# rizon.net
KiCad netlist of a schematic drawn in EAGLE
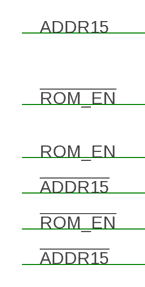
[diagram p0: schematic, sheet 1, part 1 of 2]
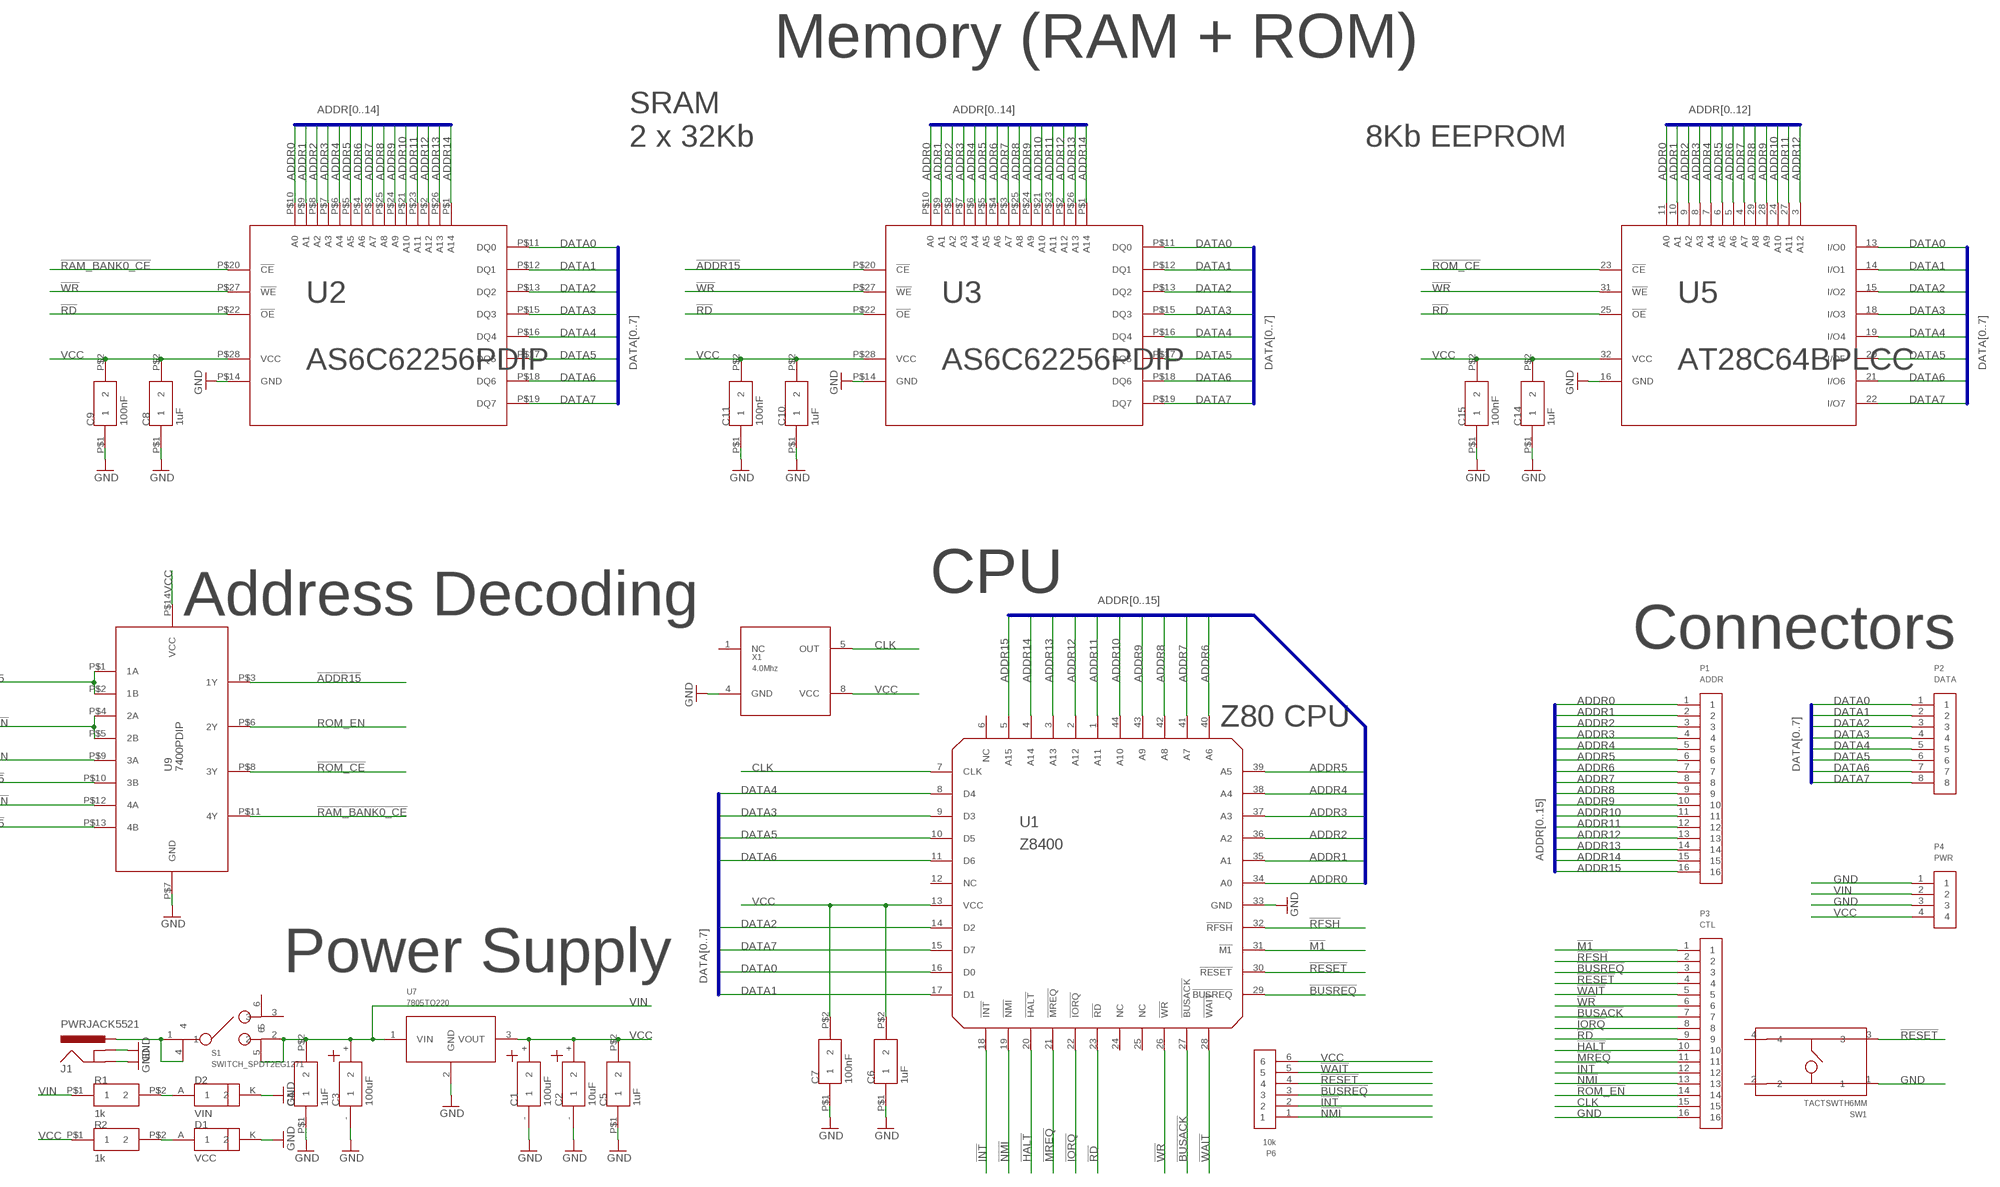
[diagram p1: schematic, sheet 1, part 2 of 2]

(export (version "E")
  (design (tool "Eeschema 10.0.6"))
  (components
    (comp (ref "C1")
      (value "100uF")
      (footprint "eagle-import:RADCAP_5MM")
      (libsource (lib "eagle-import") (part "CAP_POLARIZEDRAD_5MM"))
    )
    (comp (ref "C2")
      (value "10uF")
      (footprint "eagle-import:RADCAP_5MM")
      (libsource (lib "eagle-import") (part "CAP_POLARIZEDRAD_5MM"))
    )
    (comp (ref "C3")
      (value "100uF")
      (footprint "eagle-import:RADCAP_5MM")
      (libsource (lib "eagle-import") (part "CAP_POLARIZEDRAD_5MM"))
    )
    (comp (ref "C4")
      (value "1uF")
      (footprint "eagle-import:CAP_508")
      (libsource (lib "eagle-import") (part "CAP508"))
    )
    (comp (ref "C5")
      (value "1uF")
      (footprint "eagle-import:CAP_508")
      (libsource (lib "eagle-import") (part "CAP508"))
    )
    (comp (ref "C6")
      (value "1uF")
      (footprint "eagle-import:CAP_508")
      (libsource (lib "eagle-import") (part "CAP508"))
    )
    (comp (ref "C7")
      (value "100nF")
      (footprint "eagle-import:CAP_DISC")
      (libsource (lib "eagle-import") (part "CAPDISC"))
    )
    (comp (ref "C8")
      (value "1uF")
      (footprint "eagle-import:CAP_508")
      (libsource (lib "eagle-import") (part "CAP508"))
    )
    (comp (ref "C9")
      (value "100nF")
      (footprint "eagle-import:CAP_DISC")
      (libsource (lib "eagle-import") (part "CAPDISC"))
    )
    (comp (ref "C10")
      (value "1uF")
      (footprint "eagle-import:CAP_508")
      (libsource (lib "eagle-import") (part "CAP508"))
    )
    (comp (ref "C11")
      (value "100nF")
      (footprint "eagle-import:CAP_DISC")
      (libsource (lib "eagle-import") (part "CAPDISC"))
    )
    (comp (ref "C14")
      (value "1uF")
      (footprint "eagle-import:CAP_508")
      (libsource (lib "eagle-import") (part "CAP508"))
    )
    (comp (ref "C15")
      (value "100nF")
      (footprint "eagle-import:CAP_DISC")
      (libsource (lib "eagle-import") (part "CAPDISC"))
    )
    (comp (ref "D1")
      (value "VCC")
      (footprint "eagle-import:LED5MM")
      (libsource (lib "eagle-import") (part "LED5MM"))
    )
    (comp (ref "D2")
      (value "VIN")
      (footprint "eagle-import:LED5MM")
      (libsource (lib "eagle-import") (part "LED5MM"))
    )
    (comp (ref "J1")
      (value "PWRJACK5521")
      (footprint "eagle-import:PWRJACK_5521")
      (libsource (lib "eagle-import") (part "PWRJACK5521"))
    )
    (comp (ref "P1")
      (value "ADDR")
      (footprint "eagle-import:PIN_16")
      (libsource (lib "eagle-import") (part "PIN_16"))
    )
    (comp (ref "P2")
      (value "DATA")
      (footprint "eagle-import:PIN_8")
      (libsource (lib "eagle-import") (part "PIN_8"))
    )
    (comp (ref "P3")
      (value "CTL")
      (footprint "eagle-import:PIN_16")
      (libsource (lib "eagle-import") (part "PIN_16"))
    )
    (comp (ref "P4")
      (value "PWR")
      (footprint "eagle-import:PIN_4")
      (libsource (lib "eagle-import") (part "PIN_4"))
    )
    (comp (ref "P6")
      (value "10k")
      (footprint "eagle-import:PIN_6")
      (libsource (lib "eagle-import") (part "PIN_61LINE"))
    )
    (comp (ref "R1")
      (value "1k")
      (footprint "eagle-import:RES8MM")
      (libsource (lib "eagle-import") (part "RES8MM"))
    )
    (comp (ref "R2")
      (value "1k")
      (footprint "eagle-import:RES8MM")
      (libsource (lib "eagle-import") (part "RES8MM"))
    )
    (comp (ref "S1")
      (value "SWITCH_SPDT2EG1271")
      (footprint "eagle-import:EG1271")
      (libsource (lib "eagle-import") (part "SWITCH_SPDT2EG1271"))
    )
    (comp (ref "SW1")
      (value "TACTSWTH6MM")
      (footprint "eagle-import:SWITCH_6MM")
      (libsource (lib "eagle-import") (part "TACTSWTH6MM"))
    )
    (comp (ref "U1")
      (value "Z8400")
      (footprint "eagle-import:PLCC-S44-SOCKET")
      (libsource (lib "eagle-import") (part "Z8400"))
    )
    (comp (ref "U2")
      (value "AS6C62256PDIP")
      (footprint "eagle-import:PDIP28-600")
      (libsource (lib "eagle-import") (part "AS6C62256PDIP"))
    )
    (comp (ref "U3")
      (value "AS6C62256PDIP")
      (footprint "eagle-import:PDIP28-600")
      (libsource (lib "eagle-import") (part "AS6C62256PDIP"))
    )
    (comp (ref "U5")
      (value "AT28C64BPLCC")
      (footprint "eagle-import:PLCC-S32--SOCKET")
      (libsource (lib "eagle-import") (part "AT28C64BPLCC"))
    )
    (comp (ref "U7")
      (value "7805TO220")
      (footprint "eagle-import:TO220V")
      (libsource (lib "eagle-import") (part "7805TO220"))
    )
    (comp (ref "U9")
      (value "7400PDIP")
      (footprint "eagle-import:PDIP14")
      (libsource (lib "eagle-import") (part "7400PDIP"))
    )
    (comp (ref "X1")
      (value "4.0Mhz")
      (footprint "eagle-import:OSC127")
      (libsource (lib "eagle-import") (part "OSC412.7"))
    )
  )
  (nets
    (net (code "1") (name "/ADDR0") (class "Default")
      (node (ref "P1") (pin "1") (pinfunction "1_1") (pintype "bidirectional"))
      (node (ref "U1") (pin "34") (pinfunction "A0_34") (pintype "bidirectional"))
      (node (ref "U2") (pin "P$10") (pinfunction "A0_P$10") (pintype "bidirectional"))
      (node (ref "U3") (pin "P$10") (pinfunction "A0_P$10") (pintype "bidirectional"))
      (node (ref "U5") (pin "11") (pinfunction "A0_11") (pintype "bidirectional"))
    )
    (net (code "2") (name "/ADDR1") (class "Default")
      (node (ref "P1") (pin "2") (pinfunction "2_2") (pintype "bidirectional"))
      (node (ref "U1") (pin "35") (pinfunction "A1_35") (pintype "bidirectional"))
      (node (ref "U2") (pin "P$9") (pinfunction "A1_P$9") (pintype "bidirectional"))
      (node (ref "U3") (pin "P$9") (pinfunction "A1_P$9") (pintype "bidirectional"))
      (node (ref "U5") (pin "10") (pinfunction "A1_10") (pintype "bidirectional"))
    )
    (net (code "3") (name "/ADDR2") (class "Default")
      (node (ref "P1") (pin "3") (pinfunction "3_3") (pintype "bidirectional"))
      (node (ref "U1") (pin "36") (pinfunction "A2_36") (pintype "bidirectional"))
      (node (ref "U2") (pin "P$8") (pinfunction "A2_P$8") (pintype "bidirectional"))
      (node (ref "U3") (pin "P$8") (pinfunction "A2_P$8") (pintype "bidirectional"))
      (node (ref "U5") (pin "9") (pinfunction "A2_9") (pintype "bidirectional"))
    )
    (net (code "4") (name "/ADDR3") (class "Default")
      (node (ref "P1") (pin "4") (pinfunction "4_4") (pintype "bidirectional"))
      (node (ref "U1") (pin "37") (pinfunction "A3_37") (pintype "bidirectional"))
      (node (ref "U2") (pin "P$7") (pinfunction "A3_P$7") (pintype "bidirectional"))
      (node (ref "U3") (pin "P$7") (pinfunction "A3_P$7") (pintype "bidirectional"))
      (node (ref "U5") (pin "8") (pinfunction "A3_8") (pintype "bidirectional"))
    )
    (net (code "5") (name "/ADDR4") (class "Default")
      (node (ref "P1") (pin "5") (pinfunction "5_5") (pintype "bidirectional"))
      (node (ref "U1") (pin "38") (pinfunction "A4_38") (pintype "bidirectional"))
      (node (ref "U2") (pin "P$6") (pinfunction "A4_P$6") (pintype "bidirectional"))
      (node (ref "U3") (pin "P$6") (pinfunction "A4_P$6") (pintype "bidirectional"))
      (node (ref "U5") (pin "7") (pinfunction "A4_7") (pintype "bidirectional"))
    )
    (net (code "6") (name "/ADDR5") (class "Default")
      (node (ref "P1") (pin "6") (pinfunction "6_6") (pintype "bidirectional"))
      (node (ref "U1") (pin "39") (pinfunction "A5_39") (pintype "bidirectional"))
      (node (ref "U2") (pin "P$5") (pinfunction "A5_P$5") (pintype "bidirectional"))
      (node (ref "U3") (pin "P$5") (pinfunction "A5_P$5") (pintype "bidirectional"))
      (node (ref "U5") (pin "6") (pinfunction "A5_6") (pintype "bidirectional"))
    )
    (net (code "7") (name "/ADDR6") (class "Default")
      (node (ref "P1") (pin "7") (pinfunction "7_7") (pintype "bidirectional"))
      (node (ref "U1") (pin "40") (pinfunction "A6_40") (pintype "bidirectional"))
      (node (ref "U2") (pin "P$4") (pinfunction "A6_P$4") (pintype "bidirectional"))
      (node (ref "U3") (pin "P$4") (pinfunction "A6_P$4") (pintype "bidirectional"))
      (node (ref "U5") (pin "5") (pinfunction "A6_5") (pintype "bidirectional"))
    )
    (net (code "8") (name "/ADDR7") (class "Default")
      (node (ref "P1") (pin "8") (pinfunction "8_8") (pintype "bidirectional"))
      (node (ref "U1") (pin "41") (pinfunction "A7_41") (pintype "bidirectional"))
      (node (ref "U2") (pin "P$3") (pinfunction "A7_P$3") (pintype "bidirectional"))
      (node (ref "U3") (pin "P$3") (pinfunction "A7_P$3") (pintype "bidirectional"))
      (node (ref "U5") (pin "4") (pinfunction "A7_4") (pintype "bidirectional"))
    )
    (net (code "9") (name "/ADDR8") (class "Default")
      (node (ref "P1") (pin "9") (pinfunction "9_9") (pintype "bidirectional"))
      (node (ref "U1") (pin "42") (pinfunction "A8_42") (pintype "bidirectional"))
      (node (ref "U2") (pin "P$25") (pinfunction "A8_P$25") (pintype "bidirectional"))
      (node (ref "U3") (pin "P$25") (pinfunction "A8_P$25") (pintype "bidirectional"))
      (node (ref "U5") (pin "29") (pinfunction "A8_29") (pintype "bidirectional"))
    )
    (net (code "10") (name "/ADDR9") (class "Default")
      (node (ref "P1") (pin "10") (pinfunction "10_10") (pintype "bidirectional"))
      (node (ref "U1") (pin "43") (pinfunction "A9_43") (pintype "bidirectional"))
      (node (ref "U2") (pin "P$24") (pinfunction "A9_P$24") (pintype "bidirectional"))
      (node (ref "U3") (pin "P$24") (pinfunction "A9_P$24") (pintype "bidirectional"))
      (node (ref "U5") (pin "28") (pinfunction "A9_28") (pintype "bidirectional"))
    )
    (net (code "11") (name "/ADDR10") (class "Default")
      (node (ref "P1") (pin "11") (pinfunction "11_11") (pintype "bidirectional"))
      (node (ref "U1") (pin "44") (pinfunction "A10_44") (pintype "bidirectional"))
      (node (ref "U2") (pin "P$21") (pinfunction "A10_P$21") (pintype "bidirectional"))
      (node (ref "U3") (pin "P$21") (pinfunction "A10_P$21") (pintype "bidirectional"))
      (node (ref "U5") (pin "24") (pinfunction "A10_24") (pintype "bidirectional"))
    )
    (net (code "12") (name "/ADDR11") (class "Default")
      (node (ref "P1") (pin "12") (pinfunction "12_12") (pintype "bidirectional"))
      (node (ref "U1") (pin "1") (pinfunction "A11_1") (pintype "bidirectional"))
      (node (ref "U2") (pin "P$23") (pinfunction "A11_P$23") (pintype "bidirectional"))
      (node (ref "U3") (pin "P$23") (pinfunction "A11_P$23") (pintype "bidirectional"))
      (node (ref "U5") (pin "27") (pinfunction "A11_27") (pintype "bidirectional"))
    )
    (net (code "13") (name "/ADDR12") (class "Default")
      (node (ref "P1") (pin "13") (pinfunction "13_13") (pintype "bidirectional"))
      (node (ref "U1") (pin "2") (pinfunction "A12_2") (pintype "bidirectional"))
      (node (ref "U2") (pin "P$2") (pinfunction "A12_P$2") (pintype "bidirectional"))
      (node (ref "U3") (pin "P$2") (pinfunction "A12_P$2") (pintype "bidirectional"))
      (node (ref "U5") (pin "3") (pinfunction "A12_3") (pintype "bidirectional"))
    )
    (net (code "14") (name "/ADDR13") (class "Default")
      (node (ref "P1") (pin "14") (pinfunction "14_14") (pintype "bidirectional"))
      (node (ref "U1") (pin "3") (pinfunction "A13_3") (pintype "bidirectional"))
      (node (ref "U2") (pin "P$26") (pinfunction "A13_P$26") (pintype "bidirectional"))
      (node (ref "U3") (pin "P$26") (pinfunction "A13_P$26") (pintype "bidirectional"))
    )
    (net (code "15") (name "/ADDR14") (class "Default")
      (node (ref "P1") (pin "15") (pinfunction "15_15") (pintype "bidirectional"))
      (node (ref "U1") (pin "4") (pinfunction "A14_4") (pintype "bidirectional"))
      (node (ref "U2") (pin "P$1") (pinfunction "A14_P$1") (pintype "bidirectional"))
      (node (ref "U3") (pin "P$1") (pinfunction "A14_P$1") (pintype "bidirectional"))
    )
    (net (code "16") (name "/ADDR15") (class "Default")
      (node (ref "P1") (pin "16") (pinfunction "16_16") (pintype "bidirectional"))
      (node (ref "U1") (pin "5") (pinfunction "A15_5") (pintype "bidirectional"))
      (node (ref "U9") (pin "P$1") (pinfunction "1A_P$1") (pintype "bidirectional"))
      (node (ref "U9") (pin "P$2") (pinfunction "1B_P$2") (pintype "bidirectional"))
    )
    (net (code "20") (name "/CLK") (class "Default")
      (node (ref "P3") (pin "15") (pinfunction "15_15") (pintype "bidirectional"))
      (node (ref "U1") (pin "7") (pinfunction "CLK_7") (pintype "bidirectional"))
      (node (ref "X1") (pin "5") (pinfunction "OUT_5") (pintype "bidirectional"))
    )
    (net (code "21") (name "/DATA0") (class "Default")
      (node (ref "P2") (pin "1") (pinfunction "1_1") (pintype "bidirectional"))
      (node (ref "U1") (pin "16") (pinfunction "D0_16") (pintype "bidirectional"))
      (node (ref "U2") (pin "P$11") (pinfunction "DQ0_P$11") (pintype "bidirectional"))
      (node (ref "U3") (pin "P$11") (pinfunction "DQ0_P$11") (pintype "bidirectional"))
      (node (ref "U5") (pin "13") (pinfunction "I/O0_13") (pintype "bidirectional"))
    )
    (net (code "22") (name "/DATA1") (class "Default")
      (node (ref "P2") (pin "2") (pinfunction "2_2") (pintype "bidirectional"))
      (node (ref "U1") (pin "17") (pinfunction "D1_17") (pintype "bidirectional"))
      (node (ref "U2") (pin "P$12") (pinfunction "DQ1_P$12") (pintype "bidirectional"))
      (node (ref "U3") (pin "P$12") (pinfunction "DQ1_P$12") (pintype "bidirectional"))
      (node (ref "U5") (pin "14") (pinfunction "I/O1_14") (pintype "bidirectional"))
    )
    (net (code "23") (name "/DATA2") (class "Default")
      (node (ref "P2") (pin "3") (pinfunction "3_3") (pintype "bidirectional"))
      (node (ref "U1") (pin "14") (pinfunction "D2_14") (pintype "bidirectional"))
      (node (ref "U2") (pin "P$13") (pinfunction "DQ2_P$13") (pintype "bidirectional"))
      (node (ref "U3") (pin "P$13") (pinfunction "DQ2_P$13") (pintype "bidirectional"))
      (node (ref "U5") (pin "15") (pinfunction "I/O2_15") (pintype "bidirectional"))
    )
    (net (code "24") (name "/DATA3") (class "Default")
      (node (ref "P2") (pin "4") (pinfunction "4_4") (pintype "bidirectional"))
      (node (ref "U1") (pin "9") (pinfunction "D3_9") (pintype "bidirectional"))
      (node (ref "U2") (pin "P$15") (pinfunction "DQ3_P$15") (pintype "bidirectional"))
      (node (ref "U3") (pin "P$15") (pinfunction "DQ3_P$15") (pintype "bidirectional"))
      (node (ref "U5") (pin "18") (pinfunction "I/O3_18") (pintype "bidirectional"))
    )
    (net (code "25") (name "/DATA4") (class "Default")
      (node (ref "P2") (pin "5") (pinfunction "5_5") (pintype "bidirectional"))
      (node (ref "U1") (pin "8") (pinfunction "D4_8") (pintype "bidirectional"))
      (node (ref "U2") (pin "P$16") (pinfunction "DQ4_P$16") (pintype "bidirectional"))
      (node (ref "U3") (pin "P$16") (pinfunction "DQ4_P$16") (pintype "bidirectional"))
      (node (ref "U5") (pin "19") (pinfunction "I/O4_19") (pintype "bidirectional"))
    )
    (net (code "26") (name "/DATA5") (class "Default")
      (node (ref "P2") (pin "6") (pinfunction "6_6") (pintype "bidirectional"))
      (node (ref "U1") (pin "10") (pinfunction "D5_10") (pintype "bidirectional"))
      (node (ref "U2") (pin "P$17") (pinfunction "DQ5_P$17") (pintype "bidirectional"))
      (node (ref "U3") (pin "P$17") (pinfunction "DQ5_P$17") (pintype "bidirectional"))
      (node (ref "U5") (pin "20") (pinfunction "I/O5_20") (pintype "bidirectional"))
    )
    (net (code "27") (name "/DATA6") (class "Default")
      (node (ref "P2") (pin "7") (pinfunction "7_7") (pintype "bidirectional"))
      (node (ref "U1") (pin "11") (pinfunction "D6_11") (pintype "bidirectional"))
      (node (ref "U2") (pin "P$18") (pinfunction "DQ6_P$18") (pintype "bidirectional"))
      (node (ref "U3") (pin "P$18") (pinfunction "DQ6_P$18") (pintype "bidirectional"))
      (node (ref "U5") (pin "21") (pinfunction "I/O6_21") (pintype "bidirectional"))
    )
    (net (code "28") (name "/DATA7") (class "Default")
      (node (ref "P2") (pin "8") (pinfunction "8_8") (pintype "bidirectional"))
      (node (ref "U1") (pin "15") (pinfunction "D7_15") (pintype "bidirectional"))
      (node (ref "U2") (pin "P$19") (pinfunction "DQ7_P$19") (pintype "bidirectional"))
      (node (ref "U3") (pin "P$19") (pinfunction "DQ7_P$19") (pintype "bidirectional"))
      (node (ref "U5") (pin "22") (pinfunction "I/O7_22") (pintype "bidirectional"))
    )
    (net (code "30") (name "/ROM_EN") (class "Default")
      (node (ref "U9") (pin "P$6") (pinfunction "2Y_P$6") (pintype "bidirectional"))
      (node (ref "U9") (pin "P$9") (pinfunction "3A_P$9") (pintype "bidirectional"))
    )
    (net (code "31") (name "/VCC") (class "Default")
      (node (ref "C1") (pin "+") (pinfunction "2_+") (pintype "bidirectional"))
      (node (ref "C10") (pin "P$2") (pinfunction "2_P$2") (pintype "bidirectional"))
      (node (ref "C11") (pin "P$2") (pinfunction "2_P$2") (pintype "bidirectional"))
      (node (ref "C14") (pin "P$2") (pinfunction "2_P$2") (pintype "bidirectional"))
      (node (ref "C15") (pin "P$2") (pinfunction "2_P$2") (pintype "bidirectional"))
      (node (ref "C2") (pin "+") (pinfunction "2_+") (pintype "bidirectional"))
      (node (ref "C5") (pin "P$2") (pinfunction "2_P$2") (pintype "bidirectional"))
      (node (ref "C6") (pin "P$2") (pinfunction "2_P$2") (pintype "bidirectional"))
      (node (ref "C7") (pin "P$2") (pinfunction "2_P$2") (pintype "bidirectional"))
      (node (ref "C8") (pin "P$2") (pinfunction "2_P$2") (pintype "bidirectional"))
      (node (ref "C9") (pin "P$2") (pinfunction "2_P$2") (pintype "bidirectional"))
      (node (ref "P4") (pin "4") (pinfunction "4_4") (pintype "bidirectional"))
      (node (ref "P6") (pin "6") (pinfunction "6_6") (pintype "bidirectional"))
      (node (ref "R2") (pin "P$1") (pinfunction "1_P$1") (pintype "bidirectional"))
      (node (ref "U1") (pin "13") (pinfunction "VCC_13") (pintype "bidirectional"))
      (node (ref "U2") (pin "P$28") (pinfunction "VCC_P$28") (pintype "bidirectional"))
      (node (ref "U3") (pin "P$28") (pinfunction "VCC_P$28") (pintype "bidirectional"))
      (node (ref "U5") (pin "32") (pinfunction "VCC_32") (pintype "bidirectional"))
      (node (ref "U7") (pin "3") (pinfunction "VOUT_3") (pintype "bidirectional"))
      (node (ref "U9") (pin "P$14") (pinfunction "VCC_P$14") (pintype "bidirectional"))
      (node (ref "X1") (pin "8") (pinfunction "VCC_8") (pintype "bidirectional"))
    )
    (net (code "32") (name "/VIN") (class "Default")
      (node (ref "C3") (pin "+") (pinfunction "2_+") (pintype "bidirectional"))
      (node (ref "C4") (pin "P$2") (pinfunction "2_P$2") (pintype "bidirectional"))
      (node (ref "P4") (pin "2") (pinfunction "2_2") (pintype "bidirectional"))
      (node (ref "R1") (pin "P$1") (pinfunction "1_P$1") (pintype "bidirectional"))
      (node (ref "S1") (pin "2") (pinfunction "2_2") (pintype "bidirectional"))
      (node (ref "S1") (pin "5") (pinfunction "5_5") (pintype "bidirectional"))
      (node (ref "U7") (pin "1") (pinfunction "VIN_1") (pintype "bidirectional"))
    )
    (net (code "33") (name "/~{ADDR15}") (class "Default")
      (node (ref "U3") (pin "P$20") (pinfunction "~{CE}_P$20") (pintype "bidirectional"))
      (node (ref "U9") (pin "P$10") (pinfunction "3B_P$10") (pintype "bidirectional"))
      (node (ref "U9") (pin "P$13") (pinfunction "4B_P$13") (pintype "bidirectional"))
      (node (ref "U9") (pin "P$3") (pinfunction "1Y_P$3") (pintype "bidirectional"))
    )
    (net (code "34") (name "/~{BUSACK}") (class "Default")
      (node (ref "P3") (pin "7") (pinfunction "7_7") (pintype "bidirectional"))
      (node (ref "U1") (pin "27") (pinfunction "~{BUSACK}_27") (pintype "bidirectional"))
    )
    (net (code "35") (name "/~{BUSREQ}") (class "Default")
      (node (ref "P3") (pin "3") (pinfunction "3_3") (pintype "bidirectional"))
      (node (ref "P6") (pin "3") (pinfunction "3_3") (pintype "bidirectional"))
      (node (ref "U1") (pin "29") (pinfunction "~{BUSREQ}_29") (pintype "bidirectional"))
    )
    (net (code "36") (name "/~{HALT}") (class "Default")
      (node (ref "P3") (pin "10") (pinfunction "10_10") (pintype "bidirectional"))
      (node (ref "U1") (pin "20") (pinfunction "~{HALT}_20") (pintype "bidirectional"))
    )
    (net (code "37") (name "/~{INT}") (class "Default")
      (node (ref "P3") (pin "12") (pinfunction "12_12") (pintype "bidirectional"))
      (node (ref "P6") (pin "2") (pinfunction "2_2") (pintype "bidirectional"))
      (node (ref "U1") (pin "18") (pinfunction "~{INT}_18") (pintype "bidirectional"))
    )
    (net (code "38") (name "/~{IORQ}") (class "Default")
      (node (ref "P3") (pin "8") (pinfunction "8_8") (pintype "bidirectional"))
      (node (ref "U1") (pin "22") (pinfunction "~{IORQ}_22") (pintype "bidirectional"))
    )
    (net (code "39") (name "/~{M1}") (class "Default")
      (node (ref "P3") (pin "1") (pinfunction "1_1") (pintype "bidirectional"))
      (node (ref "U1") (pin "31") (pinfunction "~{M1}_31") (pintype "bidirectional"))
    )
    (net (code "40") (name "/~{MREQ}") (class "Default")
      (node (ref "P3") (pin "11") (pinfunction "11_11") (pintype "bidirectional"))
      (node (ref "U1") (pin "21") (pinfunction "~{MREQ}_21") (pintype "bidirectional"))
    )
    (net (code "41") (name "/~{NMI}") (class "Default")
      (node (ref "P3") (pin "13") (pinfunction "13_13") (pintype "bidirectional"))
      (node (ref "P6") (pin "1") (pinfunction "1_1") (pintype "bidirectional"))
      (node (ref "U1") (pin "19") (pinfunction "~{NMI}_19") (pintype "bidirectional"))
    )
    (net (code "42") (name "/~{RAM_BANK0_CE}") (class "Default")
      (node (ref "U2") (pin "P$20") (pinfunction "~{CE}_P$20") (pintype "bidirectional"))
      (node (ref "U9") (pin "P$11") (pinfunction "4Y_P$11") (pintype "bidirectional"))
    )
    (net (code "43") (name "/~{RD}") (class "Default")
      (node (ref "P3") (pin "9") (pinfunction "9_9") (pintype "bidirectional"))
      (node (ref "U1") (pin "23") (pinfunction "~{RD}_23") (pintype "bidirectional"))
      (node (ref "U2") (pin "P$22") (pinfunction "~{OE}_P$22") (pintype "bidirectional"))
      (node (ref "U3") (pin "P$22") (pinfunction "~{OE}_P$22") (pintype "bidirectional"))
      (node (ref "U5") (pin "25") (pinfunction "~{OE}_25") (pintype "bidirectional"))
    )
    (net (code "44") (name "/~{RESET}") (class "Default")
      (node (ref "P3") (pin "4") (pinfunction "4_4") (pintype "bidirectional"))
      (node (ref "P6") (pin "4") (pinfunction "4_4") (pintype "bidirectional"))
      (node (ref "SW1") (pin "3") (pinfunction "3_3") (pintype "bidirectional"))
      (node (ref "U1") (pin "30") (pinfunction "~{RESET}_30") (pintype "bidirectional"))
    )
    (net (code "45") (name "/~{RFSH}") (class "Default")
      (node (ref "P3") (pin "2") (pinfunction "2_2") (pintype "bidirectional"))
      (node (ref "U1") (pin "32") (pinfunction "~{RFSH}_32") (pintype "bidirectional"))
    )
    (net (code "46") (name "/~{ROM_CE}") (class "Default")
      (node (ref "U5") (pin "23") (pinfunction "~{CE}_23") (pintype "bidirectional"))
      (node (ref "U9") (pin "P$8") (pinfunction "3Y_P$8") (pintype "bidirectional"))
    )
    (net (code "47") (name "/~{ROM_EN}") (class "Default")
      (node (ref "P3") (pin "14") (pinfunction "14_14") (pintype "bidirectional"))
      (node (ref "U9") (pin "P$12") (pinfunction "4A_P$12") (pintype "bidirectional"))
      (node (ref "U9") (pin "P$4") (pinfunction "2A_P$4") (pintype "bidirectional"))
      (node (ref "U9") (pin "P$5") (pinfunction "2B_P$5") (pintype "bidirectional"))
    )
    (net (code "48") (name "/~{WAIT}") (class "Default")
      (node (ref "P3") (pin "5") (pinfunction "5_5") (pintype "bidirectional"))
      (node (ref "P6") (pin "5") (pinfunction "5_5") (pintype "bidirectional"))
      (node (ref "U1") (pin "28") (pinfunction "~{WAIT}_28") (pintype "bidirectional"))
    )
    (net (code "49") (name "/~{WR}") (class "Default")
      (node (ref "P3") (pin "6") (pinfunction "6_6") (pintype "bidirectional"))
      (node (ref "U1") (pin "26") (pinfunction "~{WR}_26") (pintype "bidirectional"))
      (node (ref "U2") (pin "P$27") (pinfunction "~{WE}_P$27") (pintype "bidirectional"))
      (node (ref "U3") (pin "P$27") (pinfunction "~{WE}_P$27") (pintype "bidirectional"))
      (node (ref "U5") (pin "31") (pinfunction "~{WE}_31") (pintype "bidirectional"))
    )
    (net (code "50") (name "GND") (class "Default")
      (node (ref "C1") (pin "-") (pinfunction "1_-") (pintype "bidirectional"))
      (node (ref "C10") (pin "P$1") (pinfunction "1_P$1") (pintype "bidirectional"))
      (node (ref "C11") (pin "P$1") (pinfunction "1_P$1") (pintype "bidirectional"))
      (node (ref "C14") (pin "P$1") (pinfunction "1_P$1") (pintype "bidirectional"))
      (node (ref "C15") (pin "P$1") (pinfunction "1_P$1") (pintype "bidirectional"))
      (node (ref "C2") (pin "-") (pinfunction "1_-") (pintype "bidirectional"))
      (node (ref "C3") (pin "-") (pinfunction "1_-") (pintype "bidirectional"))
      (node (ref "C4") (pin "P$1") (pinfunction "1_P$1") (pintype "bidirectional"))
      (node (ref "C5") (pin "P$1") (pinfunction "1_P$1") (pintype "bidirectional"))
      (node (ref "C6") (pin "P$1") (pinfunction "1_P$1") (pintype "bidirectional"))
      (node (ref "C7") (pin "P$1") (pinfunction "1_P$1") (pintype "bidirectional"))
      (node (ref "C8") (pin "P$1") (pinfunction "1_P$1") (pintype "bidirectional"))
      (node (ref "C9") (pin "P$1") (pinfunction "1_P$1") (pintype "bidirectional"))
      (node (ref "D1") (pin "K") (pinfunction "2_K") (pintype "bidirectional"))
      (node (ref "D2") (pin "K") (pinfunction "2_K") (pintype "bidirectional"))
      (node (ref "J1") (pin "GND") (pinfunction "GND_GND") (pintype "bidirectional"))
      (node (ref "J1") (pin "GNDBREAK") (pinfunction "GNDBREAK_GNDBREAK") (pintype "bidirectional"))
      (node (ref "P3") (pin "16") (pinfunction "16_16") (pintype "bidirectional"))
      (node (ref "P4") (pin "1") (pinfunction "1_1") (pintype "bidirectional"))
      (node (ref "P4") (pin "3") (pinfunction "3_3") (pintype "bidirectional"))
      (node (ref "SW1") (pin "1") (pinfunction "1_1") (pintype "bidirectional"))
      (node (ref "U1") (pin "33") (pinfunction "GND_33") (pintype "bidirectional"))
      (node (ref "U2") (pin "P$14") (pinfunction "GND_P$14") (pintype "bidirectional"))
      (node (ref "U3") (pin "P$14") (pinfunction "GND_P$14") (pintype "bidirectional"))
      (node (ref "U5") (pin "16") (pinfunction "GND_16") (pintype "bidirectional"))
      (node (ref "U7") (pin "2") (pinfunction "GND_2") (pintype "bidirectional"))
      (node (ref "U9") (pin "P$7") (pinfunction "GND_P$7") (pintype "bidirectional"))
      (node (ref "X1") (pin "4") (pinfunction "GND_4") (pintype "bidirectional"))
    )
    (net (code "51") (name "Net-(D1-1)") (class "Default")
      (node (ref "D1") (pin "A") (pinfunction "1_A") (pintype "bidirectional"))
      (node (ref "R2") (pin "P$2") (pinfunction "2_P$2") (pintype "bidirectional"))
    )
    (net (code "52") (name "Net-(D2-1)") (class "Default")
      (node (ref "D2") (pin "A") (pinfunction "1_A") (pintype "bidirectional"))
      (node (ref "R1") (pin "P$2") (pinfunction "2_P$2") (pintype "bidirectional"))
    )
    (net (code "53") (name "Net-(J1-PadPWR)") (class "Default")
      (node (ref "J1") (pin "PWR") (pinfunction "PWR_PWR") (pintype "bidirectional"))
      (node (ref "S1") (pin "1") (pinfunction "1_1") (pintype "bidirectional"))
      (node (ref "S1") (pin "4") (pinfunction "4_4") (pintype "bidirectional"))
    )
    (net (code "54") (name "unconnected-(S1-Pad3)") (class "Default")
      (node (ref "S1") (pin "3") (pinfunction "3_3") (pintype "bidirectional"))
    )
    (net (code "55") (name "unconnected-(S1-Pad6)") (class "Default")
      (node (ref "S1") (pin "6") (pinfunction "6_6") (pintype "bidirectional"))
    )
    (net (code "56") (name "unconnected-(SW1-Pad2)") (class "Default")
      (node (ref "SW1") (pin "2") (pinfunction "2_2") (pintype "bidirectional"))
    )
    (net (code "57") (name "unconnected-(SW1-Pad4)") (class "Default")
      (node (ref "SW1") (pin "4") (pinfunction "4_4") (pintype "bidirectional"))
    )
    (net (code "58") (name "unconnected-(U1-NC-Pad6)") (class "Default")
      (node (ref "U1") (pin "6") (pinfunction "NC_6") (pintype "bidirectional"))
    )
    (net (code "59") (name "unconnected-(U1-NC-Pad12)") (class "Default")
      (node (ref "U1") (pin "12") (pinfunction "NC_12") (pintype "bidirectional"))
    )
    (net (code "60") (name "unconnected-(U1-NC-Pad24)") (class "Default")
      (node (ref "U1") (pin "24") (pinfunction "NC_24") (pintype "bidirectional"))
    )
    (net (code "61") (name "unconnected-(U1-NC-Pad25)") (class "Default")
      (node (ref "U1") (pin "25") (pinfunction "NC_25") (pintype "bidirectional"))
    )
    (net (code "62") (name "unconnected-(X1-NC-Pad1)") (class "Default")
      (node (ref "X1") (pin "1") (pinfunction "NC_1") (pintype "bidirectional"))
    )
  )
)
